# Analog_Section.net
KiCad netlist of a schematic drawn in Altium Designer
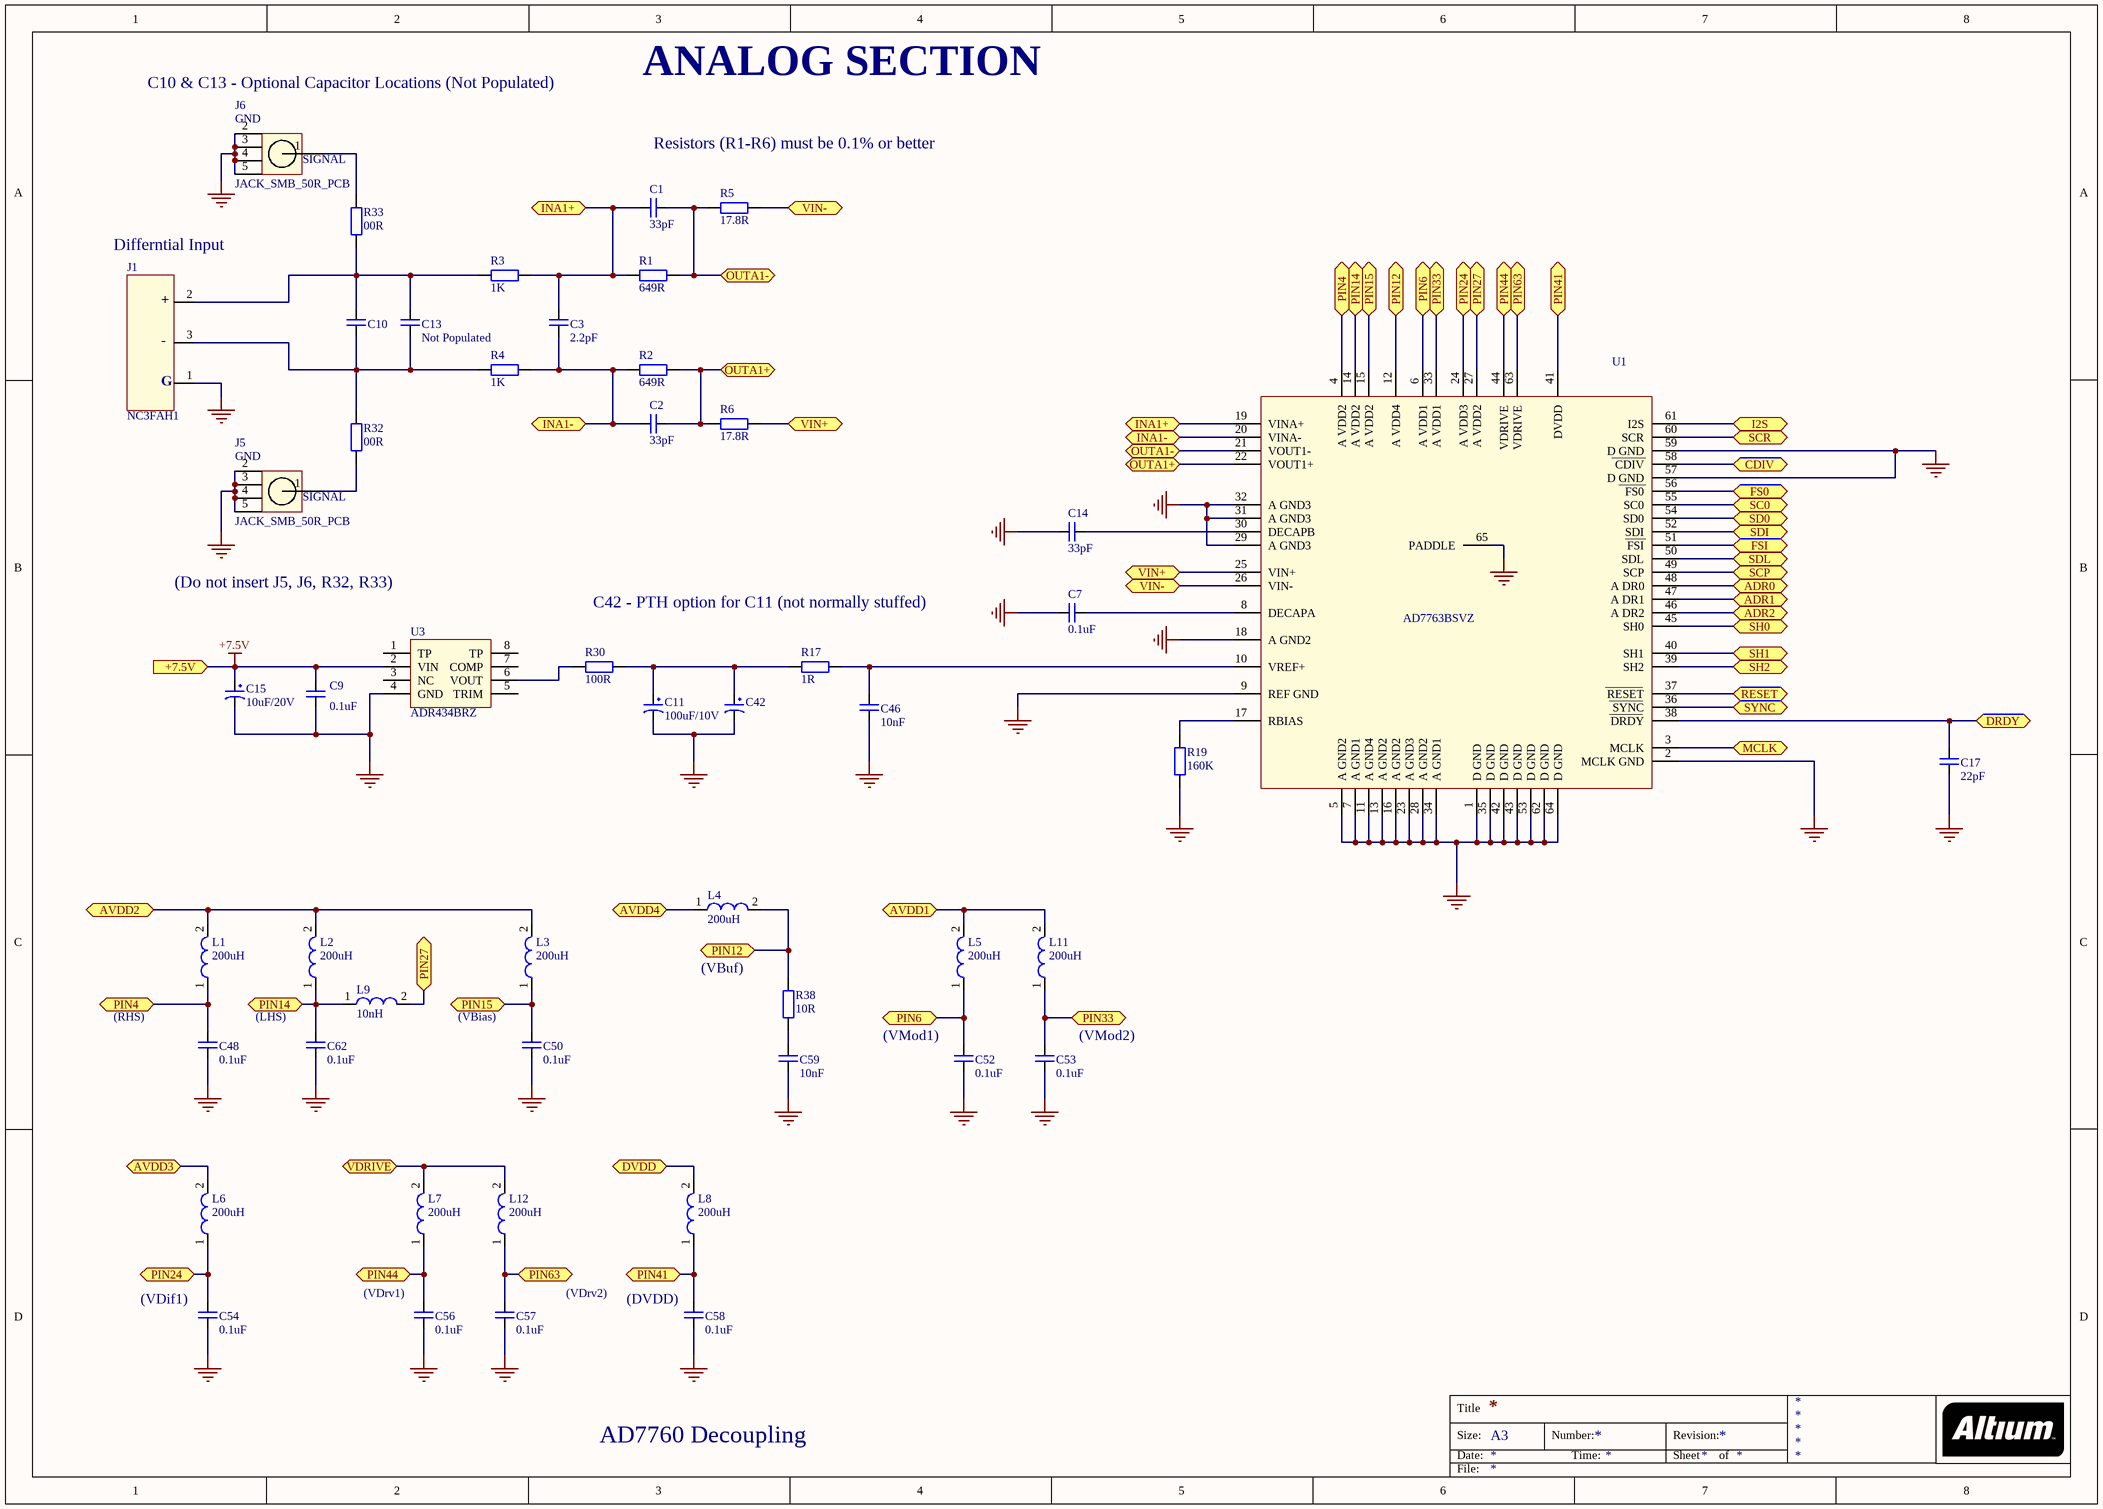
[diagram p0: Analog Section.SchDoc]

(export (version "E")
  (design (tool "Eeschema 10.0.6"))
  (components
    (comp (ref "C1")
      (value "33pF")
      (footprint "C0603")
      (description "CAP CER 33PF 50V 5% NP0 0603")
      (fields
        (field (name "MANUFACTURER") "AVX Corporation")
        (field (name "MANUFACTURER PART NUMBER") "06035A330JAT2A")
      )
      (libsource (lib "AD7763EDZ_Schematics Library") (part "C_0603_33pF"))
    )
    (comp (ref "C2")
      (value "33pF")
      (footprint "C0603")
      (description "CAP CER 33PF 50V 5% NP0 0603")
      (fields
        (field (name "MANUFACTURER") "AVX Corporation")
        (field (name "MANUFACTURER PART NUMBER") "06035A330JAT2A")
      )
      (libsource (lib "AD7763EDZ_Schematics Library") (part "C_0603_33pF"))
    )
    (comp (ref "C3")
      (value "2.2pF")
      (footprint "C0603")
      (description "CAP CER 2.2PF 50V NP0 0603")
      (fields
        (field (name "MANUFACTURER") "AVX Corporation")
        (field (name "MANUFACTURER PART NUMBER") "06035A2R2CAT2A")
      )
      (libsource (lib "AD7763EDZ_Schematics Library") (part "C_0603_2.2pF"))
    )
    (comp (ref "C7")
      (value "0.1uF")
      (footprint "C_0603")
      (description "CAP CER 0.1UF 16V Y5V 0402")
      (fields
        (field (name "MANUFACTURER") "Yageo")
        (field (name "MANUFACTURER PART NUMBER") "CC0402ZRY5V7BB104")
      )
      (libsource (lib "AD7763EDZ_Schematics Library") (part "C_0.1uF_0402"))
    )
    (comp (ref "C9")
      (value "0.1uF")
      (footprint "C0603")
      (description "Ceramic Capacitor, 0.1 µF, ± 10%, X7R, 16 V, 0603")
      (fields
        (field (name "MANUFACTURER") "MULTICOMP")
        (field (name "MANUFACTURER PART NUMBER") "MCB0603R104KCT")
      )
      (libsource (lib "AD7763EDZ_Schematics Library") (part "C_0.1uF_0603"))
    )
    (comp (ref "C10")
      (value "~")
      (footprint "C_0805")
      (description "CAP CER 0.1UF 50V 10% X7R 0805")
      (fields
        (field (name "MANUFACTURER") "MULTICOMP")
        (field (name "MANUFACTURER PART NUMBER") "MCU0805R104KCT")
      )
      (libsource (lib "AD7763EDZ_Schematics Library") (part "C_0.1uF_0805"))
    )
    (comp (ref "C11")
      (value "100uF/10V")
      (footprint "C_TANTA_TAJ-C")
      (description "CAP TANT 100UF 10V 10% 2312_TAJ-C")
      (fields
        (field (name "MANUFACTURER") "AVX Corporation")
        (field (name "MANUFACTURER PART NUMBER") "TAJC107K010RNJ")
      )
      (libsource (lib "AD7763EDZ_Schematics Library") (part "C_TANTA_100uF_10V"))
    )
    (comp (ref "C13")
      (value "Not Populated")
      (footprint "Capacitor Locations")
      (description "CAP CER 0.1UF 50V 10% X7R 0805")
      (fields
        (field (name "MANUFACTURER") "MULTICOMP")
        (field (name "MANUFACTURER PART NUMBER") "MCU0805R104KCT")
      )
      (libsource (lib "AD7763EDZ_Schematics Library") (part "C_0.1uF_0805"))
    )
    (comp (ref "C14")
      (value "33pF")
      (footprint "C0603")
      (description "CAP CER 33PF 50V 5% NP0 0603")
      (fields
        (field (name "MANUFACTURER") "AVX Corporation")
        (field (name "MANUFACTURER PART NUMBER") "06035A330JAT2A")
      )
      (libsource (lib "AD7763EDZ_Schematics Library") (part "C_0603_33pF"))
    )
    (comp (ref "C15")
      (value "10uF/20V")
      (footprint "C_TANTA_TAJ-B")
      (description "CAP TANT 10UF 20V 10% 1210")
      (fields
        (field (name "MANUFACTURER") "AVX Corporation")
        (field (name "MANUFACTURER PART NUMBER") "TAJB106K020RNJ")
      )
      (libsource (lib "AD7763EDZ_Schematics Library") (part "C_TANTA_10uF_20V"))
    )
    (comp (ref "C17")
      (value "22pF")
      (footprint "C0603")
      (description "CAP CER 22PF 50V 5% NP0 0402")
      (fields
        (field (name "MANUFACTURER") "Murata Electronics North America")
        (field (name "MANUFACTURER PART NUMBER") "GRM1555C1H220JZ01D")
      )
      (libsource (lib "AD7763EDZ_Schematics Library") (part "C_22pF_0603"))
    )
    (comp (ref "C42")
      (value "100uF/10V")
      (footprint "C_PTH_TANTA_TAJ-C")
      (description "CAP TANT 100UF 10V 10% 2312_TAJ-C")
      (fields
        (field (name "MANUFACTURER") "AVX Corporation")
        (field (name "MANUFACTURER PART NUMBER") "TAJC107K010RNJ")
      )
      (libsource (lib "AD7763EDZ_Schematics Library") (part "C_TANTA_100uF_10V"))
    )
    (comp (ref "C46")
      (value "10nF")
      (footprint "C_0402")
      (description "Cap Ceramic 0.01uF 16V X7R 10% SMD 0402")
      (fields (field (name "MANUFACTURER") "AVX") (field (name "MANUFACTURER PART NUMBER") "CM05X7R103K16AH"))
      (libsource (lib "AD7763EDZ_Schematics Library") (part "C_10nF_0402"))
    )
    (comp (ref "C48")
      (value "0.1uF")
      (footprint "C_0603")
      (description "CAP CER 0.1UF 16V Y5V 0402")
      (fields
        (field (name "MANUFACTURER") "Yageo")
        (field (name "MANUFACTURER PART NUMBER") "CC0402ZRY5V7BB104")
      )
      (libsource (lib "AD7763EDZ_Schematics Library") (part "C_0.1uF_0402"))
    )
    (comp (ref "C50")
      (value "0.1uF")
      (footprint "C_0603")
      (description "CAP CER 0.1UF 16V Y5V 0402")
      (fields
        (field (name "MANUFACTURER") "Yageo")
        (field (name "MANUFACTURER PART NUMBER") "CC0402ZRY5V7BB104")
      )
      (libsource (lib "AD7763EDZ_Schematics Library") (part "C_0.1uF_0402"))
    )
    (comp (ref "C52")
      (value "0.1uF")
      (footprint "C_0603")
      (description "CAP CER 0.1UF 16V Y5V 0402")
      (fields
        (field (name "MANUFACTURER") "Yageo")
        (field (name "MANUFACTURER PART NUMBER") "CC0402ZRY5V7BB104")
      )
      (libsource (lib "AD7763EDZ_Schematics Library") (part "C_0.1uF_0402"))
    )
    (comp (ref "C53")
      (value "0.1uF")
      (footprint "C_0603")
      (description "CAP CER 0.1UF 16V Y5V 0402")
      (fields
        (field (name "MANUFACTURER") "Yageo")
        (field (name "MANUFACTURER PART NUMBER") "CC0402ZRY5V7BB104")
      )
      (libsource (lib "AD7763EDZ_Schematics Library") (part "C_0.1uF_0402"))
    )
    (comp (ref "C54")
      (value "0.1uF")
      (footprint "C_0603")
      (description "CAP CER 0.1UF 16V Y5V 0402")
      (fields
        (field (name "MANUFACTURER") "Yageo")
        (field (name "MANUFACTURER PART NUMBER") "CC0402ZRY5V7BB104")
      )
      (libsource (lib "AD7763EDZ_Schematics Library") (part "C_0.1uF_0402"))
    )
    (comp (ref "C56")
      (value "0.1uF")
      (footprint "C0603")
      (description "Ceramic Capacitor, 0.1 µF, ± 10%, X7R, 16 V, 0603")
      (fields
        (field (name "MANUFACTURER") "MULTICOMP")
        (field (name "MANUFACTURER PART NUMBER") "MCB0603R104KCT")
      )
      (libsource (lib "AD7763EDZ_Schematics Library") (part "C_0.1uF_0603"))
    )
    (comp (ref "C57")
      (value "0.1uF")
      (footprint "C_0603")
      (description "CAP CER 0.1UF 16V Y5V 0402")
      (fields
        (field (name "MANUFACTURER") "Yageo")
        (field (name "MANUFACTURER PART NUMBER") "CC0402ZRY5V7BB104")
      )
      (libsource (lib "AD7763EDZ_Schematics Library") (part "C_0.1uF_0402"))
    )
    (comp (ref "C58")
      (value "0.1uF")
      (footprint "C0603")
      (description "Ceramic Capacitor, 0.1 µF, ± 10%, X7R, 16 V, 0603")
      (fields
        (field (name "MANUFACTURER") "MULTICOMP")
        (field (name "MANUFACTURER PART NUMBER") "MCB0603R104KCT")
      )
      (libsource (lib "AD7763EDZ_Schematics Library") (part "C_0.1uF_0603"))
    )
    (comp (ref "C59")
      (value "10nF")
      (footprint "C_0603")
      (description "CAP CER 10000PF 25V 10% X7R 0603")
      (fields
        (field (name "MANUFACTURER") "AVX Corporation")
        (field (name "MANUFACTURER PART NUMBER") "06033C103KAT2A")
      )
      (libsource (lib "AD7763EDZ_Schematics Library") (part "C_10nF_0603"))
    )
    (comp (ref "C62")
      (value "0.1uF")
      (footprint "C0603")
      (description "Ceramic Capacitor, 0.1 µF, ± 10%, X7R, 16 V, 0603")
      (fields
        (field (name "MANUFACTURER") "MULTICOMP")
        (field (name "MANUFACTURER PART NUMBER") "MCB0603R104KCT")
      )
      (libsource (lib "AD7763EDZ_Schematics Library") (part "C_0.1uF_0603"))
    )
    (comp (ref "J1")
      (value "NC3FAH1")
      (footprint "NC3FAH1_Audio")
      (description "XLR Female Audio Connector NC3FAH1-1")
      (fields (field (name "MANUFACTURER") "Neutrik"))
      (libsource (lib "AD7763EDZ_Schematics Library") (part "XLR_Female"))
    )
    (comp (ref "J5")
      (value "JACK_SMB_50R_PCB")
      (footprint "SMB Jack Radial")
      (description "CONN SMB JACK STR 50 OHM PCB")
      (fields (field (name "MANUFACTURER") "RADIALL") (field (name "MANUFACTURER PART NUMBER") "R114426000"))
      (libsource (lib "AD7763EDZ_Schematics Library") (part "JACK_SMB_50R_PCB"))
    )
    (comp (ref "J6")
      (value "JACK_SMB_50R_PCB")
      (footprint "SMB Jack Radial")
      (description "CONN SMB JACK STR 50 OHM PCB")
      (fields (field (name "MANUFACTURER") "RADIALL") (field (name "MANUFACTURER PART NUMBER") "R114426000"))
      (libsource (lib "AD7763EDZ_Schematics Library") (part "JACK_SMB_50R_PCB"))
    )
    (comp (ref "L1")
      (value "200uH")
      (footprint "IND_0603")
      (description "FERRITE BEAD 1000 OHM 0.2A 0603")
      (fields
        (field (name "MANUFACTURER") "Wurth Electronics Inc")
        (field (name "MANUFACTURER PART NUMBER") "74279266")
      )
      (libsource (lib "AD7763EDZ_Schematics Library") (part "FERRITE_BEAT_200uH"))
    )
    (comp (ref "L2")
      (value "200uH")
      (footprint "IND_0603")
      (description "FERRITE BEAD 1000 OHM 0.2A 0603")
      (fields
        (field (name "MANUFACTURER") "Wurth Electronics Inc")
        (field (name "MANUFACTURER PART NUMBER") "74279266")
      )
      (libsource (lib "AD7763EDZ_Schematics Library") (part "FERRITE_BEAT_200uH"))
    )
    (comp (ref "L3")
      (value "200uH")
      (footprint "IND_0603")
      (description "FERRITE BEAD 1000 OHM 0.2A 0603")
      (fields
        (field (name "MANUFACTURER") "Wurth Electronics Inc")
        (field (name "MANUFACTURER PART NUMBER") "74279266")
      )
      (libsource (lib "AD7763EDZ_Schematics Library") (part "FERRITE_BEAT_200uH"))
    )
    (comp (ref "L4")
      (value "200uH")
      (footprint "IND_0603")
      (description "FERRITE BEAD 1000 OHM 0.2A 0603")
      (fields
        (field (name "MANUFACTURER") "Wurth Electronics Inc")
        (field (name "MANUFACTURER PART NUMBER") "74279266")
      )
      (libsource (lib "AD7763EDZ_Schematics Library") (part "FERRITE_BEAT_200uH"))
    )
    (comp (ref "L5")
      (value "200uH")
      (footprint "IND_0603")
      (description "FERRITE BEAD 1000 OHM 0.2A 0603")
      (fields
        (field (name "MANUFACTURER") "Wurth Electronics Inc")
        (field (name "MANUFACTURER PART NUMBER") "74279266")
      )
      (libsource (lib "AD7763EDZ_Schematics Library") (part "FERRITE_BEAT_200uH"))
    )
    (comp (ref "L6")
      (value "200uH")
      (footprint "IND_0603")
      (description "FERRITE BEAD 1000 OHM 0.2A 0603")
      (fields
        (field (name "MANUFACTURER") "Wurth Electronics Inc")
        (field (name "MANUFACTURER PART NUMBER") "74279266")
      )
      (libsource (lib "AD7763EDZ_Schematics Library") (part "FERRITE_BEAT_200uH"))
    )
    (comp (ref "L7")
      (value "200uH")
      (footprint "IND_0603")
      (description "FERRITE BEAD 1000 OHM 0.2A 0603")
      (fields
        (field (name "MANUFACTURER") "Wurth Electronics Inc")
        (field (name "MANUFACTURER PART NUMBER") "74279266")
      )
      (libsource (lib "AD7763EDZ_Schematics Library") (part "FERRITE_BEAT_200uH"))
    )
    (comp (ref "L8")
      (value "200uH")
      (footprint "IND_0603")
      (description "FERRITE BEAD 1000 OHM 0.2A 0603")
      (fields
        (field (name "MANUFACTURER") "Wurth Electronics Inc")
        (field (name "MANUFACTURER PART NUMBER") "74279266")
      )
      (libsource (lib "AD7763EDZ_Schematics Library") (part "FERRITE_BEAT_200uH"))
    )
    (comp (ref "L9")
      (value "10nH")
      (footprint "IND_0603")
      (description "FIXED IND 10NH 600MA 200 MOHM")
      (fields
        (field (name "MANUFACTURER") "EPCOS (TDK)")
        (field (name "MANUFACTURER PART NUMBER") "B82496C3100J")
      )
      (libsource (lib "AD7763EDZ_Schematics Library") (part "FERRITE_BEAT_10nH"))
    )
    (comp (ref "L11")
      (value "200uH")
      (footprint "IND_0603")
      (description "FERRITE BEAD 1000 OHM 0.2A 0603")
      (fields
        (field (name "MANUFACTURER") "Wurth Electronics Inc")
        (field (name "MANUFACTURER PART NUMBER") "74279266")
      )
      (libsource (lib "AD7763EDZ_Schematics Library") (part "FERRITE_BEAT_200uH"))
    )
    (comp (ref "L12")
      (value "200uH")
      (footprint "IND_0603")
      (description "FERRITE BEAD 1000 OHM 0.2A 0603")
      (fields
        (field (name "MANUFACTURER") "Wurth Electronics Inc")
        (field (name "MANUFACTURER PART NUMBER") "74279266")
      )
      (libsource (lib "AD7763EDZ_Schematics Library") (part "FERRITE_BEAT_200uH"))
    )
    (comp (ref "R1")
      (value "649R")
      (footprint "R_0603")
      (description "RES SMD 649 OHM 0.1% 1/16W 0603")
      (fields
        (field (name "MANUFACTURER") "TE Connectivity AMP Connectors")
        (field (name "MANUFACTURER PART NUMBER") "3-1614354-7")
      )
      (libsource (lib "AD7763EDZ_Schematics Library") (part "R_0603_649R"))
    )
    (comp (ref "R2")
      (value "649R")
      (footprint "R_0603")
      (description "RES SMD 649 OHM 0.1% 1/16W 0603")
      (fields
        (field (name "MANUFACTURER") "TE Connectivity AMP Connectors")
        (field (name "MANUFACTURER PART NUMBER") "3-1614354-7")
      )
      (libsource (lib "AD7763EDZ_Schematics Library") (part "R_0603_649R"))
    )
    (comp (ref "R3")
      (value "1K")
      (footprint "R_0603")
      (description "RES SMD 1K OHM 0.1% 1/16W 0603")
      (fields
        (field (name "MANUFACTURER") "TE Connectivity AMP Connectors")
        (field (name "MANUFACTURER PART NUMBER") "1-1614351-9")
      )
      (libsource (lib "AD7763EDZ_Schematics Library") (part "R_0603_1K"))
    )
    (comp (ref "R4")
      (value "1K")
      (footprint "R_0603")
      (description "RES SMD 1K OHM 0.1% 1/16W 0603")
      (fields
        (field (name "MANUFACTURER") "TE Connectivity AMP Connectors")
        (field (name "MANUFACTURER PART NUMBER") "1-1614351-9")
      )
      (libsource (lib "AD7763EDZ_Schematics Library") (part "R_0603_1K"))
    )
    (comp (ref "R5")
      (value "17.8R")
      (footprint "R_0603")
      (description "RES SMD 17.8 OHM 0.1% 1/16W 0603")
      (fields
        (field (name "MANUFACTURER") "TE Connectivity AMP Connectors")
        (field (name "MANUFACTURER PART NUMBER") "6-1614350-6")
      )
      (libsource (lib "AD7763EDZ_Schematics Library") (part "R_0603_17.8R"))
    )
    (comp (ref "R6")
      (value "17.8R")
      (footprint "R_0603")
      (description "RES SMD 17.8 OHM 0.1% 1/16W 0603")
      (fields
        (field (name "MANUFACTURER") "TE Connectivity AMP Connectors")
        (field (name "MANUFACTURER PART NUMBER") "6-1614350-6")
      )
      (libsource (lib "AD7763EDZ_Schematics Library") (part "R_0603_17.8R"))
    )
    (comp (ref "R17")
      (value "1R")
      (footprint "R_0603")
      (description "RES SMD 1 OHM 1% 1/16W 0603")
      (fields
        (field (name "MANUFACTURER") "MULTICOMP")
        (field (name "MANUFACTURER PART NUMBER") "MC0063W060311R0")
      )
      (libsource (lib "AD7763EDZ_Schematics Library") (part "R_0603_1R"))
    )
    (comp (ref "R19")
      (value "160K")
      (footprint "R_0603")
      (description "RES SMD 160K OHM 1% 1/10W 0603")
      (fields
        (field (name "MANUFACTURER") "MULTICOMP")
        (field (name "MANUFACTURER PART NUMBER") "MC0063W06031160K")
      )
      (libsource (lib "AD7763EDZ_Schematics Library") (part "R_0603_160K"))
    )
    (comp (ref "R30")
      (value "100R")
      (footprint "R_0603")
      (description "RES SMD 100 OHM 1% 1/16W 0603")
      (fields
        (field (name "MANUFACTURER") "MULTICOMP")
        (field (name "MANUFACTURER PART NUMBER") "MC0063W06031100R")
      )
      (libsource (lib "AD7763EDZ_Schematics Library") (part "R_0603_100R"))
    )
    (comp (ref "R32")
      (value "00R")
      (footprint "R_0603")
      (description "RES SMD 0.0 OHM JUMPER 1/16W")
      (fields
        (field (name "MANUFACTURER") "TE Connectivity AMP Connectors")
        (field (name "MANUFACTURER PART NUMBER") "6-1622826-4")
      )
      (libsource (lib "AD7763EDZ_Schematics Library") (part "R_0603_00R"))
    )
    (comp (ref "R33")
      (value "00R")
      (footprint "R_0603")
      (description "RES SMD 0.0 OHM JUMPER 1/16W")
      (fields
        (field (name "MANUFACTURER") "TE Connectivity AMP Connectors")
        (field (name "MANUFACTURER PART NUMBER") "6-1622826-4")
      )
      (libsource (lib "AD7763EDZ_Schematics Library") (part "R_0603_00R"))
    )
    (comp (ref "R38")
      (value "10R")
      (footprint "R_0603")
      (description "RES SMD 10R OHM 1% 1/16W 0603")
      (fields
        (field (name "MANUFACTURER") "MULTICOMP")
        (field (name "MANUFACTURER PART NUMBER") "MC0063W0603110R")
      )
      (libsource (lib "AD7763EDZ_Schematics Library") (part "R_0603_10R"))
    )
    (comp (ref "U1")
      (value "AD7763BSVZ")
      (footprint "TQFP-64")
      (description "IC ADC 24BIT SRL 625KSPS 64TQFP")
      (fields (field (name "MANUFACTURER") "Analog Devices Inc"))
      (libsource (lib "AD7763EDZ_Schematics Library") (part "AD7763BSVZ"))
    )
    (comp (ref "U3")
      (value "ADR434BRZ")
      (footprint "SOIC-8")
      (description "IC VREF SERIES 4.096V 8SOIC")
      (fields (field (name "MANUFACTURER") "Analog Devices Inc") (field (name "TOLERANCE") "±0.04%"))
      (libsource (lib "AD7763EDZ_Schematics Library") (part "ADR434BRZ"))
    )
  )
  (nets
    (net (code "1") (name "+7.5V") (class "Default")
      (node (ref "C15") (pin "1") (pinfunction "1_1") (pintype "passive"))
      (node (ref "C9") (pin "1") (pinfunction "1_1") (pintype "passive"))
      (node (ref "U3") (pin "2") (pinfunction "VIN_2") (pintype "passive"))
    )
    (net (code "2") (name "/ADR0") (class "Default")
      (node (ref "U1") (pin "48") (pinfunction "A_DR0_48") (pintype "passive"))
    )
    (net (code "3") (name "/ADR1") (class "Default")
      (node (ref "U1") (pin "47") (pinfunction "A_DR1_47") (pintype "passive"))
    )
    (net (code "4") (name "/ADR2") (class "Default")
      (node (ref "U1") (pin "46") (pinfunction "A_DR2_46") (pintype "passive"))
    )
    (net (code "5") (name "/AVDD1") (class "Default")
      (node (ref "L11") (pin "2") (pinfunction "2_2") (pintype "passive"))
      (node (ref "L5") (pin "2") (pinfunction "2_2") (pintype "passive"))
    )
    (net (code "6") (name "/AVDD2") (class "Default")
      (node (ref "L1") (pin "2") (pinfunction "2_2") (pintype "passive"))
      (node (ref "L2") (pin "2") (pinfunction "2_2") (pintype "passive"))
      (node (ref "L3") (pin "2") (pinfunction "2_2") (pintype "passive"))
    )
    (net (code "7") (name "/AVDD3") (class "Default")
      (node (ref "L6") (pin "2") (pinfunction "2_2") (pintype "passive"))
    )
    (net (code "8") (name "/AVDD4") (class "Default")
      (node (ref "L4") (pin "1") (pinfunction "1_1") (pintype "passive"))
    )
    (net (code "9") (name "/CDIV") (class "Default")
      (node (ref "U1") (pin "58") (pinfunction "CDIV_58") (pintype "passive"))
    )
    (net (code "10") (name "/DRDY") (class "Default")
      (node (ref "C17") (pin "1") (pinfunction "1_1") (pintype "passive"))
      (node (ref "U1") (pin "38") (pinfunction "DRDY_38") (pintype "passive"))
    )
    (net (code "11") (name "/DVDD") (class "Default")
      (node (ref "L8") (pin "2") (pinfunction "2_2") (pintype "passive"))
    )
    (net (code "12") (name "/FS0") (class "Default")
      (node (ref "U1") (pin "56") (pinfunction "FS0_56") (pintype "passive"))
    )
    (net (code "13") (name "/FSI") (class "Default")
      (node (ref "U1") (pin "51") (pinfunction "FSI_51") (pintype "passive"))
    )
    (net (code "14") (name "/I2S") (class "Default")
      (node (ref "U1") (pin "61") (pinfunction "I2S_61") (pintype "passive"))
    )
    (net (code "15") (name "/INA1+") (class "Default")
      (node (ref "C1") (pin "1") (pinfunction "1_1") (pintype "passive"))
      (node (ref "C3") (pin "1") (pinfunction "1_1") (pintype "passive"))
      (node (ref "R1") (pin "1") (pinfunction "1_1") (pintype "passive"))
      (node (ref "R3") (pin "2") (pinfunction "2_2") (pintype "passive"))
      (node (ref "U1") (pin "19") (pinfunction "VINA+_19") (pintype "passive"))
    )
    (net (code "16") (name "/INA1-") (class "Default")
      (node (ref "C2") (pin "1") (pinfunction "1_1") (pintype "passive"))
      (node (ref "C3") (pin "2") (pinfunction "2_2") (pintype "passive"))
      (node (ref "R2") (pin "1") (pinfunction "1_1") (pintype "passive"))
      (node (ref "R4") (pin "2") (pinfunction "2_2") (pintype "passive"))
      (node (ref "U1") (pin "20") (pinfunction "VINA-_20") (pintype "passive"))
    )
    (net (code "17") (name "/MCLK") (class "Default")
      (node (ref "U1") (pin "3") (pinfunction "MCLK_3") (pintype "passive"))
    )
    (net (code "18") (name "/OUTA1+") (class "Default")
      (node (ref "C2") (pin "2") (pinfunction "2_2") (pintype "passive"))
      (node (ref "R2") (pin "2") (pinfunction "2_2") (pintype "passive"))
      (node (ref "R6") (pin "1") (pinfunction "1_1") (pintype "passive"))
      (node (ref "U1") (pin "22") (pinfunction "VOUT1+_22") (pintype "passive"))
    )
    (net (code "19") (name "/OUTA1-") (class "Default")
      (node (ref "C1") (pin "2") (pinfunction "2_2") (pintype "passive"))
      (node (ref "R1") (pin "2") (pinfunction "2_2") (pintype "passive"))
      (node (ref "R5") (pin "1") (pinfunction "1_1") (pintype "passive"))
      (node (ref "U1") (pin "21") (pinfunction "VOUT1-_21") (pintype "passive"))
    )
    (net (code "20") (name "/PIN4") (class "Default")
      (node (ref "C48") (pin "1") (pinfunction "1_1") (pintype "passive"))
      (node (ref "L1") (pin "1") (pinfunction "1_1") (pintype "passive"))
      (node (ref "U1") (pin "4") (pinfunction "A_VDD2_4") (pintype "passive"))
    )
    (net (code "21") (name "/PIN6") (class "Default")
      (node (ref "C52") (pin "1") (pinfunction "1_1") (pintype "passive"))
      (node (ref "L5") (pin "1") (pinfunction "1_1") (pintype "passive"))
      (node (ref "U1") (pin "6") (pinfunction "A_VDD1_6") (pintype "passive"))
    )
    (net (code "22") (name "/PIN12") (class "Default")
      (node (ref "L4") (pin "2") (pinfunction "2_2") (pintype "passive"))
      (node (ref "R38") (pin "2") (pinfunction "2_2") (pintype "passive"))
      (node (ref "U1") (pin "12") (pinfunction "A_VDD4_12") (pintype "passive"))
    )
    (net (code "23") (name "/PIN14") (class "Default")
      (node (ref "C62") (pin "1") (pinfunction "1_1") (pintype "passive"))
      (node (ref "L2") (pin "1") (pinfunction "1_1") (pintype "passive"))
      (node (ref "L9") (pin "1") (pinfunction "1_1") (pintype "passive"))
      (node (ref "U1") (pin "14") (pinfunction "A_VDD2_14") (pintype "passive"))
    )
    (net (code "24") (name "/PIN15") (class "Default")
      (node (ref "C50") (pin "1") (pinfunction "1_1") (pintype "passive"))
      (node (ref "L3") (pin "1") (pinfunction "1_1") (pintype "passive"))
      (node (ref "U1") (pin "15") (pinfunction "A_VDD2_15") (pintype "passive"))
    )
    (net (code "25") (name "/PIN24") (class "Default")
      (node (ref "C54") (pin "1") (pinfunction "1_1") (pintype "passive"))
      (node (ref "L6") (pin "1") (pinfunction "1_1") (pintype "passive"))
      (node (ref "U1") (pin "24") (pinfunction "A_VDD3_24") (pintype "passive"))
    )
    (net (code "26") (name "/PIN27") (class "Default")
      (node (ref "L9") (pin "2") (pinfunction "2_2") (pintype "passive"))
      (node (ref "U1") (pin "27") (pinfunction "A_VDD2_27") (pintype "passive"))
    )
    (net (code "27") (name "/PIN33") (class "Default")
      (node (ref "C53") (pin "1") (pinfunction "1_1") (pintype "passive"))
      (node (ref "L11") (pin "1") (pinfunction "1_1") (pintype "passive"))
      (node (ref "U1") (pin "33") (pinfunction "A_VDD1_33") (pintype "passive"))
    )
    (net (code "28") (name "/PIN41") (class "Default")
      (node (ref "C58") (pin "1") (pinfunction "1_1") (pintype "passive"))
      (node (ref "L8") (pin "1") (pinfunction "1_1") (pintype "passive"))
      (node (ref "U1") (pin "41") (pinfunction "DVDD_41") (pintype "passive"))
    )
    (net (code "29") (name "/PIN44") (class "Default")
      (node (ref "C56") (pin "1") (pinfunction "1_1") (pintype "passive"))
      (node (ref "L7") (pin "1") (pinfunction "1_1") (pintype "passive"))
      (node (ref "U1") (pin "44") (pinfunction "VDRIVE_44") (pintype "passive"))
    )
    (net (code "30") (name "/PIN63") (class "Default")
      (node (ref "C57") (pin "1") (pinfunction "1_1") (pintype "passive"))
      (node (ref "L12") (pin "1") (pinfunction "1_1") (pintype "passive"))
      (node (ref "U1") (pin "63") (pinfunction "VDRIVE_63") (pintype "passive"))
    )
    (net (code "31") (name "/RESET") (class "Default")
      (node (ref "U1") (pin "37") (pinfunction "RESET_37") (pintype "passive"))
    )
    (net (code "32") (name "/SC0") (class "Default")
      (node (ref "U1") (pin "55") (pinfunction "SC0_55") (pintype "passive"))
    )
    (net (code "33") (name "/SCP") (class "Default")
      (node (ref "U1") (pin "49") (pinfunction "SCP_49") (pintype "passive"))
    )
    (net (code "34") (name "/SCR") (class "Default")
      (node (ref "U1") (pin "60") (pinfunction "SCR_60") (pintype "passive"))
    )
    (net (code "35") (name "/SD0") (class "Default")
      (node (ref "U1") (pin "54") (pinfunction "SD0_54") (pintype "passive"))
    )
    (net (code "36") (name "/SDI") (class "Default")
      (node (ref "U1") (pin "52") (pinfunction "SDI_52") (pintype "passive"))
    )
    (net (code "37") (name "/SDL") (class "Default")
      (node (ref "U1") (pin "50") (pinfunction "SDL_50") (pintype "passive"))
    )
    (net (code "38") (name "/SH0") (class "Default")
      (node (ref "U1") (pin "45") (pinfunction "SH0_45") (pintype "passive"))
    )
    (net (code "39") (name "/SH1") (class "Default")
      (node (ref "U1") (pin "40") (pinfunction "SH1_40") (pintype "passive"))
    )
    (net (code "40") (name "/SH2") (class "Default")
      (node (ref "U1") (pin "39") (pinfunction "SH2_39") (pintype "passive"))
    )
    (net (code "41") (name "/SYNC") (class "Default")
      (node (ref "U1") (pin "36") (pinfunction "SYNC_36") (pintype "passive"))
    )
    (net (code "42") (name "/VDRIVE") (class "Default")
      (node (ref "L12") (pin "2") (pinfunction "2_2") (pintype "passive"))
      (node (ref "L7") (pin "2") (pinfunction "2_2") (pintype "passive"))
    )
    (net (code "43") (name "/VIN+") (class "Default")
      (node (ref "R6") (pin "2") (pinfunction "2_2") (pintype "passive"))
      (node (ref "U1") (pin "25") (pinfunction "VIN+_25") (pintype "passive"))
    )
    (net (code "44") (name "/VIN-") (class "Default")
      (node (ref "R5") (pin "2") (pinfunction "2_2") (pintype "passive"))
      (node (ref "U1") (pin "26") (pinfunction "VIN-_26") (pintype "passive"))
    )
    (net (code "45") (name "<NO NET>") (class "Default")
      (node (ref "C11") (pin "2") (pinfunction "2_2") (pintype "passive"))
      (node (ref "C14") (pin "1") (pinfunction "1_1") (pintype "passive"))
      (node (ref "C15") (pin "2") (pinfunction "2_2") (pintype "passive"))
      (node (ref "C17") (pin "2") (pinfunction "2_2") (pintype "passive"))
      (node (ref "C42") (pin "2") (pinfunction "2_2") (pintype "passive"))
      (node (ref "C46") (pin "2") (pinfunction "2_2") (pintype "passive"))
      (node (ref "C48") (pin "2") (pinfunction "2_2") (pintype "passive"))
      (node (ref "C50") (pin "2") (pinfunction "2_2") (pintype "passive"))
      (node (ref "C52") (pin "2") (pinfunction "2_2") (pintype "passive"))
      (node (ref "C53") (pin "2") (pinfunction "2_2") (pintype "passive"))
      (node (ref "C54") (pin "2") (pinfunction "2_2") (pintype "passive"))
      (node (ref "C56") (pin "2") (pinfunction "2_2") (pintype "passive"))
      (node (ref "C57") (pin "2") (pinfunction "2_2") (pintype "passive"))
      (node (ref "C58") (pin "2") (pinfunction "2_2") (pintype "passive"))
      (node (ref "C59") (pin "2") (pinfunction "2_2") (pintype "passive"))
      (node (ref "C62") (pin "2") (pinfunction "2_2") (pintype "passive"))
      (node (ref "C7") (pin "1") (pinfunction "1_1") (pintype "passive"))
      (node (ref "C9") (pin "2") (pinfunction "2_2") (pintype "passive"))
      (node (ref "J1") (pin "1") (pinfunction "G_1") (pintype "passive"))
      (node (ref "J5") (pin "2") (pinfunction "2_2") (pintype "power_in"))
      (node (ref "J5") (pin "3") (pinfunction "3_3") (pintype "power_in"))
      (node (ref "J5") (pin "4") (pinfunction "4_4") (pintype "power_in"))
      (node (ref "J5") (pin "5") (pinfunction "5_5") (pintype "power_in"))
      (node (ref "J6") (pin "2") (pinfunction "2_2") (pintype "power_in"))
      (node (ref "J6") (pin "3") (pinfunction "3_3") (pintype "power_in"))
      (node (ref "J6") (pin "4") (pinfunction "4_4") (pintype "power_in"))
      (node (ref "J6") (pin "5") (pinfunction "5_5") (pintype "power_in"))
      (node (ref "R19") (pin "1") (pinfunction "1_1") (pintype "passive"))
      (node (ref "U1") (pin "1") (pinfunction "D_GND_1") (pintype "passive"))
      (node (ref "U1") (pin "11") (pinfunction "A_GND4_11") (pintype "passive"))
      (node (ref "U1") (pin "13") (pinfunction "A_GND2_13") (pintype "passive"))
      (node (ref "U1") (pin "16") (pinfunction "A_GND2_16") (pintype "passive"))
      (node (ref "U1") (pin "18") (pinfunction "A_GND2_18") (pintype "passive"))
      (node (ref "U1") (pin "2") (pinfunction "MCLK_GND_2") (pintype "passive"))
      (node (ref "U1") (pin "23") (pinfunction "A_GND3_23") (pintype "passive"))
      (node (ref "U1") (pin "28") (pinfunction "A_GND2_28") (pintype "passive"))
      (node (ref "U1") (pin "29") (pinfunction "A_GND3_29") (pintype "passive"))
      (node (ref "U1") (pin "31") (pinfunction "A_GND3_31") (pintype "passive"))
      (node (ref "U1") (pin "32") (pinfunction "A_GND3_32") (pintype "passive"))
      (node (ref "U1") (pin "34") (pinfunction "A_GND1_34") (pintype "passive"))
      (node (ref "U1") (pin "35") (pinfunction "D_GND_35") (pintype "passive"))
      (node (ref "U1") (pin "42") (pinfunction "D_GND_42") (pintype "passive"))
      (node (ref "U1") (pin "43") (pinfunction "D_GND_43") (pintype "passive"))
      (node (ref "U1") (pin "5") (pinfunction "A_GND2_5") (pintype "passive"))
      (node (ref "U1") (pin "53") (pinfunction "D_GND_53") (pintype "passive"))
      (node (ref "U1") (pin "57") (pinfunction "D_GND_57") (pintype "passive"))
      (node (ref "U1") (pin "59") (pinfunction "D_GND_59") (pintype "passive"))
      (node (ref "U1") (pin "62") (pinfunction "D_GND_62") (pintype "passive"))
      (node (ref "U1") (pin "64") (pinfunction "D_GND_64") (pintype "passive"))
      (node (ref "U1") (pin "65") (pinfunction "PADDLE_65") (pintype "passive"))
      (node (ref "U1") (pin "7") (pinfunction "A_GND1_7") (pintype "passive"))
      (node (ref "U1") (pin "9") (pinfunction "REF_GND_9") (pintype "passive"))
      (node (ref "U3") (pin "4") (pinfunction "GND_4") (pintype "passive"))
    )
    (net (code "46") (name "Net-(C11-Pad1)") (class "Default")
      (node (ref "C11") (pin "1") (pinfunction "1_1") (pintype "passive"))
      (node (ref "C42") (pin "1") (pinfunction "1_1") (pintype "passive"))
      (node (ref "R17") (pin "1") (pinfunction "1_1") (pintype "passive"))
      (node (ref "R30") (pin "2") (pinfunction "2_2") (pintype "passive"))
    )
    (net (code "47") (name "Net-(C59-Pad1)") (class "Default")
      (node (ref "C59") (pin "1") (pinfunction "1_1") (pintype "passive"))
      (node (ref "R38") (pin "1") (pinfunction "1_1") (pintype "passive"))
    )
    (net (code "48") (name "Net-(J1-+)") (class "Default")
      (node (ref "C10") (pin "1") (pinfunction "1_1") (pintype "passive"))
      (node (ref "C13") (pin "1") (pinfunction "1_1") (pintype "passive"))
      (node (ref "J1") (pin "2") (pinfunction "+_2") (pintype "passive"))
      (node (ref "R3") (pin "1") (pinfunction "1_1") (pintype "passive"))
      (node (ref "R33") (pin "1") (pinfunction "1_1") (pintype "passive"))
    )
    (net (code "49") (name "Net-(J1--)") (class "Default")
      (node (ref "C10") (pin "2") (pinfunction "2_2") (pintype "passive"))
      (node (ref "C13") (pin "2") (pinfunction "2_2") (pintype "passive"))
      (node (ref "J1") (pin "3") (pinfunction "-_3") (pintype "passive"))
      (node (ref "R32") (pin "2") (pinfunction "2_2") (pintype "passive"))
      (node (ref "R4") (pin "1") (pinfunction "1_1") (pintype "passive"))
    )
    (net (code "50") (name "Net-(J5-Pad1)") (class "Default")
      (node (ref "J5") (pin "1") (pinfunction "1_1") (pintype "passive"))
      (node (ref "R32") (pin "1") (pinfunction "1_1") (pintype "passive"))
    )
    (net (code "51") (name "Net-(J6-Pad1)") (class "Default")
      (node (ref "J6") (pin "1") (pinfunction "1_1") (pintype "passive"))
      (node (ref "R33") (pin "2") (pinfunction "2_2") (pintype "passive"))
    )
    (net (code "52") (name "Net-(U1-DECAPA)") (class "Default")
      (node (ref "C7") (pin "2") (pinfunction "2_2") (pintype "passive"))
      (node (ref "U1") (pin "8") (pinfunction "DECAPA_8") (pintype "passive"))
    )
    (net (code "53") (name "Net-(U1-DECAPB)") (class "Default")
      (node (ref "C14") (pin "2") (pinfunction "2_2") (pintype "passive"))
      (node (ref "U1") (pin "30") (pinfunction "DECAPB_30") (pintype "passive"))
    )
    (net (code "54") (name "Net-(U1-RBIAS)") (class "Default")
      (node (ref "R19") (pin "2") (pinfunction "2_2") (pintype "passive"))
      (node (ref "U1") (pin "17") (pinfunction "RBIAS_17") (pintype "passive"))
    )
    (net (code "55") (name "Net-(U1-VREF+)") (class "Default")
      (node (ref "C46") (pin "1") (pinfunction "1_1") (pintype "passive"))
      (node (ref "R17") (pin "2") (pinfunction "2_2") (pintype "passive"))
      (node (ref "U1") (pin "10") (pinfunction "VREF+_10") (pintype "passive"))
    )
    (net (code "56") (name "Net-(U3-VOUT)") (class "Default")
      (node (ref "R30") (pin "1") (pinfunction "1_1") (pintype "passive"))
      (node (ref "U3") (pin "6") (pinfunction "VOUT_6") (pintype "passive"))
    )
    (net (code "57") (name "unconnected-(U3-COMP-Pad7)") (class "Default")
      (node (ref "U3") (pin "7") (pinfunction "COMP_7") (pintype "passive"))
    )
    (net (code "58") (name "unconnected-(U3-NC-Pad3)") (class "Default")
      (node (ref "U3") (pin "3") (pinfunction "NC_3") (pintype "passive"))
    )
    (net (code "59") (name "unconnected-(U3-TP-Pad1)") (class "Default")
      (node (ref "U3") (pin "1") (pinfunction "TP_1") (pintype "passive"))
    )
    (net (code "60") (name "unconnected-(U3-TP-Pad8)") (class "Default")
      (node (ref "U3") (pin "8") (pinfunction "TP_8") (pintype "passive"))
    )
    (net (code "61") (name "unconnected-(U3-TRIM-Pad5)") (class "Default")
      (node (ref "U3") (pin "5") (pinfunction "TRIM_5") (pintype "passive"))
    )
  )
)
